# ESP32.net
KiCad netlist of a schematic drawn in Altium Designer
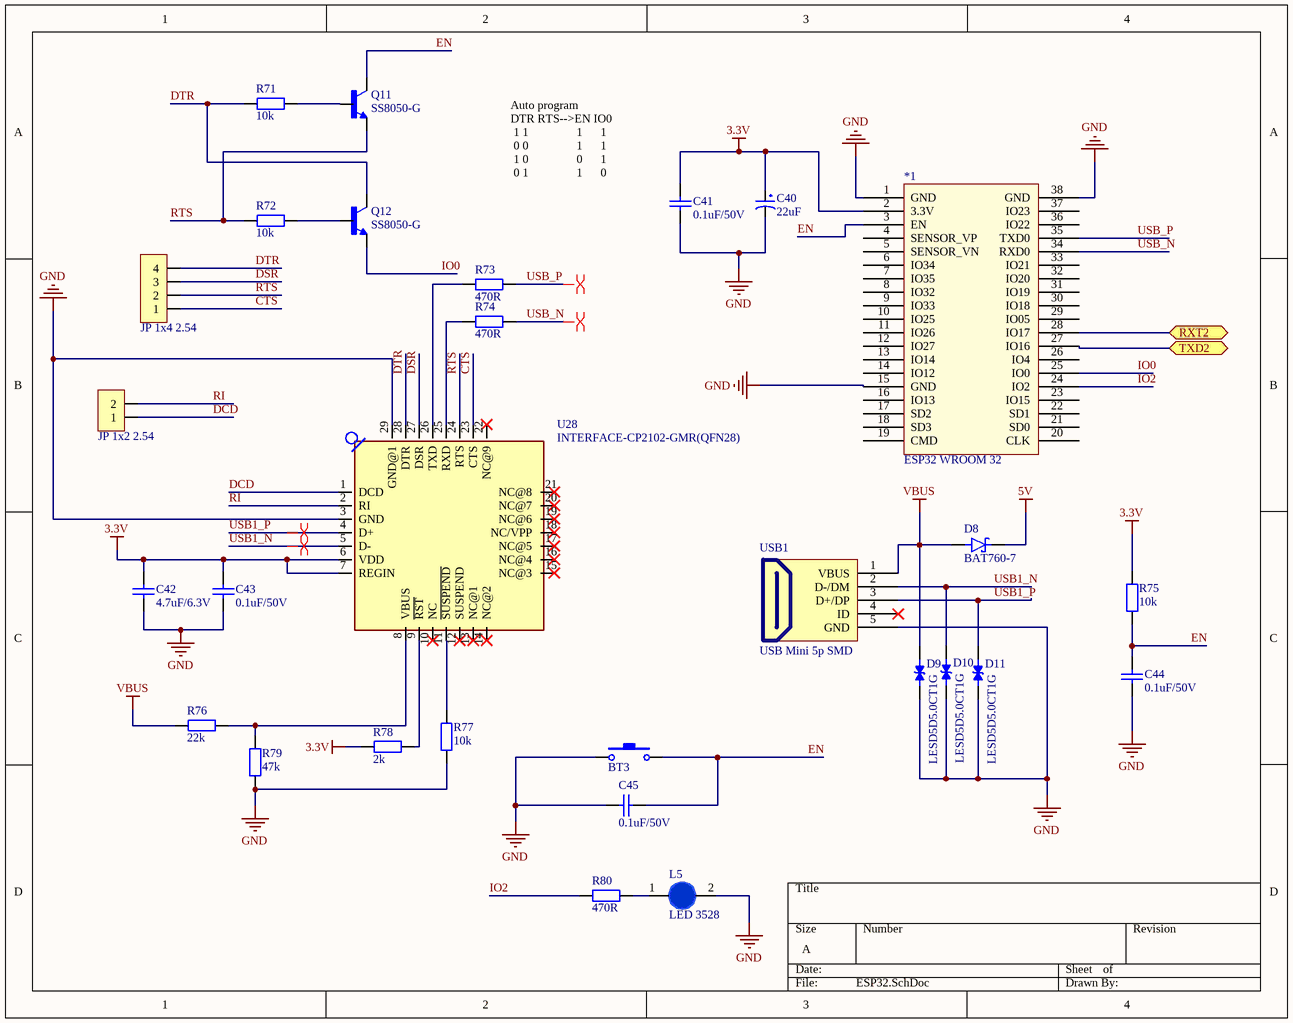
[diagram p0: ESP32.SchDoc]

(export (version "E")
  (design (tool "Eeschema 10.0.6"))
  (components
    (comp (ref "*1")
      (value "ESP32 WROOM 32")
      (footprint "ESP32-WROOM-32D")
      (libsource (lib "Altium_Lib_by_KhueNguyenCreator") (part "ESP32 WROOM 32"))
    )
    (comp (ref "BT3")
      (value "Nut Nhan 2 Chan SMD 3x6x2.5")
      (footprint "Nut Nhan 2 Chan SMD 3x6x2.5")
      (libsource (lib "Altium_Lib_by_KhueNguyenCreator") (part "Nut Nhan 2 Chan SMD 3x6x2.5"))
    )
    (comp (ref "C40")
      (value "22uF")
      (footprint "tu tantalum smd7343")
      (description "Dán")
      (libsource (lib "Altium_Lib_by_KhueNguyenCreator") (part "Tu tantalum 22uF 25V SMD7343"))
    )
    (comp (ref "C41")
      (value "0.1uF/50V")
      (footprint "tu 0805")
      (description "Dán")
      (libsource (lib "Altium_Lib_by_KhueNguyenCreator") (part "Tu 0805 104 50V 10%"))
    )
    (comp (ref "C42")
      (value "4.7uF/6.3V")
      (footprint "tu 0805")
      (description "Dán")
      (libsource (lib "Altium_Lib_by_KhueNguyenCreator") (part "Tu 0805 104 50V 10%"))
    )
    (comp (ref "C43")
      (value "0.1uF/50V")
      (footprint "tu 0805")
      (description "Dán")
      (libsource (lib "Altium_Lib_by_KhueNguyenCreator") (part "Tu 0805 104 50V 10%"))
    )
    (comp (ref "C44")
      (value "0.1uF/50V")
      (footprint "tu 0805")
      (description "Dán")
      (libsource (lib "Altium_Lib_by_KhueNguyenCreator") (part "Tu 0805 104 50V 10%"))
    )
    (comp (ref "C45")
      (value "0.1uF/50V")
      (footprint "tu 0805")
      (description "Dán")
      (libsource (lib "Altium_Lib_by_KhueNguyenCreator") (part "Tu 0805 104 50V 10%"))
    )
    (comp (ref "D8")
      (value "BAT760-7")
      (footprint "SOD2513X120N")
      (description "Diode Schottky 30V 1A 2-Pin SOD-323 T/R")
      (fields (field (name "MF") "Diodes Zetex"))
      (libsource (lib "TestLib") (part "BAT760-7"))
    )
    (comp (ref "D9")
      (value "LESD5D5.0CT1G")
      (footprint "TVS_LESD5D5.0CT1G")
      (description "Transient Voltage Suppressors for ESD Protection")
      (fields (field (name "MF") "Leshan Radio Co."))
      (libsource (lib "TestLib") (part "LESD5D5.0CT1G"))
    )
    (comp (ref "D10")
      (value "LESD5D5.0CT1G")
      (footprint "TVS_LESD5D5.0CT1G")
      (description "Transient Voltage Suppressors for ESD Protection")
      (fields (field (name "MF") "Leshan Radio Co."))
      (libsource (lib "TestLib") (part "LESD5D5.0CT1G"))
    )
    (comp (ref "D11")
      (value "LESD5D5.0CT1G")
      (footprint "TVS_LESD5D5.0CT1G")
      (description "Transient Voltage Suppressors for ESD Protection")
      (fields (field (name "MF") "Leshan Radio Co."))
      (libsource (lib "TestLib") (part "LESD5D5.0CT1G"))
    )
    (comp (ref "JP2")
      (value "JP 1x4 2.54")
      (footprint "JP 1x4 DT")
      (description "Cắm")
      (libsource (lib "Altium_Lib_by_KhueNguyenCreator") (part "JP 1x4 2.54 Duc Thang"))
    )
    (comp (ref "JP3")
      (value "JP 1x2 2.54")
      (footprint "JP 1x2 DT")
      (description "Cắm")
      (libsource (lib "Altium_Lib_by_KhueNguyenCreator") (part "JP 1x2 2.54 Duc Thang"))
    )
    (comp (ref "L5")
      (value "LED 3528")
      (footprint "LED-3528-BLUE")
      (description "Dán")
      (libsource (lib "Altium_Lib_by_KhueNguyenCreator") (part "LED 3528 Xanh Duong"))
    )
    (comp (ref "Q11")
      (value "SS8050-G")
      (footprint "TRANS_SS8050-G")
      (description "Bipolar (BJT) Transistor NPN 25 V 1.5 A 100MHz 300 mW Surface Mount SOT-23-3")
      (fields (field (name "DIGI-KEY_PART_NUMBER") "641-1790-2-ND") (field (name "MP") "SS8050G"))
      (libsource (lib "TestLib") (part "SS8050-G"))
    )
    (comp (ref "Q12")
      (value "SS8050-G")
      (footprint "TRANS_SS8050-G")
      (description "Bipolar (BJT) Transistor NPN 25 V 1.5 A 100MHz 300 mW Surface Mount SOT-23-3")
      (fields (field (name "DIGI-KEY_PART_NUMBER") "641-1790-2-ND") (field (name "MP") "SS8050G"))
      (libsource (lib "TestLib") (part "SS8050-G"))
    )
    (comp (ref "R71")
      (value "10k")
      (footprint "tro smd 0805")
      (description "Dán")
      (libsource (lib "Altium_Lib_by_KhueNguyenCreator") (part "Tro 0805 5% 10k"))
    )
    (comp (ref "R72")
      (value "10k")
      (footprint "tro smd 0805")
      (description "Dán")
      (libsource (lib "Altium_Lib_by_KhueNguyenCreator") (part "Tro 0805 5% 10k"))
    )
    (comp (ref "R73")
      (value "470R")
      (footprint "Tro SMD 0805")
      (description "Dán")
      (libsource (lib "Altium_Lib_by_KhueNguyenCreator") (part "Tro 0805 5% 470R"))
    )
    (comp (ref "R74")
      (value "470R")
      (footprint "Tro SMD 0805")
      (description "Dán")
      (libsource (lib "Altium_Lib_by_KhueNguyenCreator") (part "Tro 0805 5% 470R"))
    )
    (comp (ref "R75")
      (value "10k")
      (footprint "tro smd 0805")
      (description "Dán")
      (libsource (lib "Altium_Lib_by_KhueNguyenCreator") (part "Tro 0805 5% 10k"))
    )
    (comp (ref "R76")
      (value "22k")
      (footprint "tro smd 0805")
      (description "Dán")
      (libsource (lib "Altium_Lib_by_KhueNguyenCreator") (part "Tro 0805 5% 22k"))
    )
    (comp (ref "R77")
      (value "10k")
      (footprint "tro smd 0805")
      (description "Dán")
      (libsource (lib "Altium_Lib_by_KhueNguyenCreator") (part "Tro 0805 5% 10k"))
    )
    (comp (ref "R78")
      (value "2k")
      (footprint "Tro SMD 0805")
      (description "Dán")
      (libsource (lib "Altium_Lib_by_KhueNguyenCreator") (part "Tro 0805 5% 2k"))
    )
    (comp (ref "R79")
      (value "47k")
      (footprint "tro smd 0805")
      (description "Dán")
      (libsource (lib "Altium_Lib_by_KhueNguyenCreator") (part "Tro 0805 5% 47k"))
    )
    (comp (ref "R80")
      (value "470R")
      (footprint "Tro SMD 0805")
      (description "Dán")
      (libsource (lib "Altium_Lib_by_KhueNguyenCreator") (part "Tro 0805 5% 470R"))
    )
    (comp (ref "U28")
      (value "INTERFACE-CP2102-GMR(QFN28)")
      (footprint "QFN28G_0.5-5X5MM")
      (description "USB Bridge, USB to UART USB 2.0 UART Interface 28-QFN (5x5)")
      (fields (field (name "MP") "CP2102-GMR") (field (name "MF") "Silicon"))
      (libsource (lib "TestLib") (part "INTERFACE-CP2102-GMR(QFN28)"))
    )
    (comp (ref "USB1")
      (value "USB Mini 5p SMD")
      (footprint "USB Mini 5p SMD")
      (description "USB Type B")
      (libsource (lib "Altium_Lib_by_KhueNguyenCreator") (part "USB Mini 5p SMD"))
    )
  )
  (nets
    (net (code "1") (name "/CTS") (class "Default")
      (node (ref "JP2") (pin "1") (pinfunction "1_1") (pintype "passive"))
      (node (ref "U28") (pin "23") (pinfunction "CTS_23") (pintype "bidirectional"))
    )
    (net (code "2") (name "/DCD") (class "Default")
      (node (ref "JP3") (pin "1") (pinfunction "1_1") (pintype "passive"))
      (node (ref "U28") (pin "1") (pinfunction "DCD_1") (pintype "bidirectional"))
    )
    (net (code "3") (name "/DSR") (class "Default")
      (node (ref "JP2") (pin "3") (pinfunction "3_3") (pintype "passive"))
      (node (ref "U28") (pin "27") (pinfunction "DSR_27") (pintype "bidirectional"))
    )
    (net (code "4") (name "/DTR") (class "Default")
      (node (ref "JP2") (pin "4") (pinfunction "4_4") (pintype "passive"))
      (node (ref "Q12") (pin "3") (pinfunction "C_3") (pintype "passive"))
      (node (ref "R71") (pin "1") (pinfunction "1_1") (pintype "passive"))
      (node (ref "U28") (pin "28") (pinfunction "DTR_28") (pintype "bidirectional"))
    )
    (net (code "5") (name "/EN") (class "Default")
      (node (ref "*1") (pin "3") (pinfunction "EN_3") (pintype "passive"))
      (node (ref "BT3") (pin "2") (pinfunction "2_2") (pintype "passive"))
      (node (ref "C44") (pin "2") (pinfunction "2_2") (pintype "passive"))
      (node (ref "C45") (pin "1") (pinfunction "1_1") (pintype "passive"))
      (node (ref "Q11") (pin "3") (pinfunction "C_3") (pintype "passive"))
      (node (ref "R75") (pin "1") (pinfunction "1_1") (pintype "passive"))
    )
    (net (code "6") (name "/IO0") (class "Default")
      (node (ref "*1") (pin "25") (pinfunction "IO0_25") (pintype "passive"))
      (node (ref "Q12") (pin "2") (pinfunction "E_2") (pintype "passive"))
    )
    (net (code "7") (name "/IO2") (class "Default")
      (node (ref "*1") (pin "24") (pinfunction "IO2_24") (pintype "passive"))
      (node (ref "R80") (pin "1") (pinfunction "1_1") (pintype "passive"))
    )
    (net (code "8") (name "/RI") (class "Default")
      (node (ref "JP3") (pin "2") (pinfunction "2_2") (pintype "passive"))
      (node (ref "U28") (pin "2") (pinfunction "RI_2") (pintype "bidirectional"))
    )
    (net (code "9") (name "/RTS") (class "Default")
      (node (ref "JP2") (pin "2") (pinfunction "2_2") (pintype "passive"))
      (node (ref "Q11") (pin "2") (pinfunction "E_2") (pintype "passive"))
      (node (ref "R72") (pin "1") (pinfunction "1_1") (pintype "passive"))
      (node (ref "U28") (pin "24") (pinfunction "RTS_24") (pintype "bidirectional"))
    )
    (net (code "10") (name "/RXT2") (class "Default")
      (node (ref "*1") (pin "28") (pinfunction "IO17_28") (pintype "passive"))
    )
    (net (code "11") (name "/TXD2") (class "Default")
      (node (ref "*1") (pin "27") (pinfunction "IO16_27") (pintype "passive"))
    )
    (net (code "12") (name "/USB1_N") (class "Default")
      (node (ref "D10") (pin "1") (pinfunction "1_1") (pintype "passive"))
      (node (ref "U28") (pin "5") (pinfunction "D-_5") (pintype "bidirectional"))
      (node (ref "USB1") (pin "2") (pinfunction "D-/DM_2") (pintype "passive"))
    )
    (net (code "13") (name "/USB1_P") (class "Default")
      (node (ref "D11") (pin "1") (pinfunction "1_1") (pintype "passive"))
      (node (ref "U28") (pin "4") (pinfunction "D+_4") (pintype "bidirectional"))
      (node (ref "USB1") (pin "3") (pinfunction "D+/DP_3") (pintype "passive"))
    )
    (net (code "14") (name "/USB_N") (class "Default")
      (node (ref "*1") (pin "34") (pinfunction "RXD0_34") (pintype "passive"))
      (node (ref "R74") (pin "2") (pinfunction "2_2") (pintype "passive"))
    )
    (net (code "15") (name "/USB_P") (class "Default")
      (node (ref "*1") (pin "35") (pinfunction "TXD0_35") (pintype "passive"))
      (node (ref "R73") (pin "2") (pinfunction "2_2") (pintype "passive"))
    )
    (net (code "16") (name "3.3V") (class "Default")
      (node (ref "*1") (pin "2") (pinfunction "3.3V_2") (pintype "passive"))
      (node (ref "C40") (pin "1") (pinfunction "1_1") (pintype "passive"))
      (node (ref "C41") (pin "2") (pinfunction "2_2") (pintype "passive"))
      (node (ref "C42") (pin "1") (pinfunction "1_1") (pintype "passive"))
      (node (ref "C43") (pin "1") (pinfunction "1_1") (pintype "passive"))
      (node (ref "R75") (pin "2") (pinfunction "2_2") (pintype "passive"))
      (node (ref "R78") (pin "1") (pinfunction "1_1") (pintype "passive"))
      (node (ref "U28") (pin "6") (pinfunction "VDD_6") (pintype "bidirectional"))
      (node (ref "U28") (pin "7") (pinfunction "REGIN_7") (pintype "bidirectional"))
    )
    (net (code "17") (name "5V") (class "Default")
      (node (ref "D8") (pin "C") (pinfunction "K_C") (pintype "passive"))
    )
    (net (code "18") (name "GND") (class "Default")
      (node (ref "*1") (pin "1") (pinfunction "GND_1") (pintype "passive"))
      (node (ref "*1") (pin "15") (pinfunction "GND_15") (pintype "passive"))
      (node (ref "*1") (pin "38") (pinfunction "GND_38") (pintype "passive"))
      (node (ref "BT3") (pin "1") (pinfunction "1_1") (pintype "passive"))
      (node (ref "C40") (pin "2") (pinfunction "2_2") (pintype "passive"))
      (node (ref "C41") (pin "1") (pinfunction "1_1") (pintype "passive"))
      (node (ref "C42") (pin "2") (pinfunction "2_2") (pintype "passive"))
      (node (ref "C43") (pin "2") (pinfunction "2_2") (pintype "passive"))
      (node (ref "C44") (pin "1") (pinfunction "1_1") (pintype "passive"))
      (node (ref "C45") (pin "2") (pinfunction "2_2") (pintype "passive"))
      (node (ref "D10") (pin "2") (pinfunction "2_2") (pintype "passive"))
      (node (ref "D11") (pin "2") (pinfunction "2_2") (pintype "passive"))
      (node (ref "D9") (pin "2") (pinfunction "2_2") (pintype "passive"))
      (node (ref "L5") (pin "2") (pinfunction "K_2") (pintype "passive"))
      (node (ref "R77") (pin "1") (pinfunction "1_1") (pintype "passive"))
      (node (ref "R79") (pin "2") (pinfunction "2_2") (pintype "passive"))
      (node (ref "U28") (pin "29") (pinfunction "GND@1_29") (pintype "bidirectional"))
      (node (ref "U28") (pin "3") (pinfunction "GND_3") (pintype "bidirectional"))
      (node (ref "USB1") (pin "5") (pinfunction "GND_5") (pintype "passive"))
    )
    (net (code "19") (name "Net-(L5-A)") (class "Default")
      (node (ref "L5") (pin "1") (pinfunction "A_1") (pintype "passive"))
      (node (ref "R80") (pin "2") (pinfunction "2_2") (pintype "passive"))
    )
    (net (code "20") (name "Net-(Q11-B)") (class "Default")
      (node (ref "Q11") (pin "1") (pinfunction "B_1") (pintype "passive"))
      (node (ref "R71") (pin "2") (pinfunction "2_2") (pintype "passive"))
    )
    (net (code "21") (name "Net-(Q12-B)") (class "Default")
      (node (ref "Q12") (pin "1") (pinfunction "B_1") (pintype "passive"))
      (node (ref "R72") (pin "2") (pinfunction "2_2") (pintype "passive"))
    )
    (net (code "22") (name "Net-(U28-RXD)") (class "Default")
      (node (ref "R74") (pin "1") (pinfunction "1_1") (pintype "passive"))
      (node (ref "U28") (pin "25") (pinfunction "RXD_25") (pintype "bidirectional"))
    )
    (net (code "23") (name "Net-(U28-TXD)") (class "Default")
      (node (ref "R73") (pin "1") (pinfunction "1_1") (pintype "passive"))
      (node (ref "U28") (pin "26") (pinfunction "TXD_26") (pintype "bidirectional"))
    )
    (net (code "24") (name "Net-(U28-VBUS)") (class "Default")
      (node (ref "R76") (pin "2") (pinfunction "2_2") (pintype "passive"))
      (node (ref "R79") (pin "1") (pinfunction "1_1") (pintype "passive"))
      (node (ref "U28") (pin "8") (pinfunction "VBUS_8") (pintype "bidirectional"))
    )
    (net (code "25") (name "Net-(U28-~{RST})") (class "Default")
      (node (ref "R78") (pin "2") (pinfunction "2_2") (pintype "passive"))
      (node (ref "U28") (pin "9") (pinfunction "~{RST}_9") (pintype "bidirectional"))
    )
    (net (code "26") (name "Net-(U28-~{SUSPEND})") (class "Default")
      (node (ref "R77") (pin "2") (pinfunction "2_2") (pintype "passive"))
      (node (ref "U28") (pin "11") (pinfunction "~{SUSPEND}_11") (pintype "bidirectional"))
    )
    (net (code "27") (name "VBUS") (class "Default")
      (node (ref "D8") (pin "A") (pinfunction "A_A") (pintype "passive"))
      (node (ref "D9") (pin "1") (pinfunction "1_1") (pintype "passive"))
      (node (ref "R76") (pin "1") (pinfunction "1_1") (pintype "passive"))
      (node (ref "USB1") (pin "1") (pinfunction "VBUS_1") (pintype "passive"))
    )
    (net (code "28") (name "unconnected-(*1-CLK-Pad20)") (class "Default")
      (node (ref "*1") (pin "20") (pinfunction "CLK_20") (pintype "passive"))
    )
    (net (code "29") (name "unconnected-(*1-CMD-Pad19)") (class "Default")
      (node (ref "*1") (pin "19") (pinfunction "CMD_19") (pintype "passive"))
    )
    (net (code "30") (name "unconnected-(*1-IO4-Pad26)") (class "Default")
      (node (ref "*1") (pin "26") (pinfunction "IO4_26") (pintype "passive"))
    )
    (net (code "31") (name "unconnected-(*1-IO05-Pad29)") (class "Default")
      (node (ref "*1") (pin "29") (pinfunction "IO05_29") (pintype "passive"))
    )
    (net (code "32") (name "unconnected-(*1-IO12-Pad14)") (class "Default")
      (node (ref "*1") (pin "14") (pinfunction "IO12_14") (pintype "passive"))
    )
    (net (code "33") (name "unconnected-(*1-IO13-Pad16)") (class "Default")
      (node (ref "*1") (pin "16") (pinfunction "IO13_16") (pintype "passive"))
    )
    (net (code "34") (name "unconnected-(*1-IO14-Pad13)") (class "Default")
      (node (ref "*1") (pin "13") (pinfunction "IO14_13") (pintype "passive"))
    )
    (net (code "35") (name "unconnected-(*1-IO15-Pad23)") (class "Default")
      (node (ref "*1") (pin "23") (pinfunction "IO15_23") (pintype "passive"))
    )
    (net (code "36") (name "unconnected-(*1-IO18-Pad30)") (class "Default")
      (node (ref "*1") (pin "30") (pinfunction "IO18_30") (pintype "passive"))
    )
    (net (code "37") (name "unconnected-(*1-IO19-Pad31)") (class "Default")
      (node (ref "*1") (pin "31") (pinfunction "IO19_31") (pintype "passive"))
    )
    (net (code "38") (name "unconnected-(*1-IO20-Pad32)") (class "Default")
      (node (ref "*1") (pin "32") (pinfunction "IO20_32") (pintype "passive"))
    )
    (net (code "39") (name "unconnected-(*1-IO21-Pad33)") (class "Default")
      (node (ref "*1") (pin "33") (pinfunction "IO21_33") (pintype "passive"))
    )
    (net (code "40") (name "unconnected-(*1-IO22-Pad36)") (class "Default")
      (node (ref "*1") (pin "36") (pinfunction "IO22_36") (pintype "passive"))
    )
    (net (code "41") (name "unconnected-(*1-IO23-Pad37)") (class "Default")
      (node (ref "*1") (pin "37") (pinfunction "IO23_37") (pintype "passive"))
    )
    (net (code "42") (name "unconnected-(*1-IO25-Pad10)") (class "Default")
      (node (ref "*1") (pin "10") (pinfunction "IO25_10") (pintype "passive"))
    )
    (net (code "43") (name "unconnected-(*1-IO26-Pad11)") (class "Default")
      (node (ref "*1") (pin "11") (pinfunction "IO26_11") (pintype "passive"))
    )
    (net (code "44") (name "unconnected-(*1-IO27-Pad12)") (class "Default")
      (node (ref "*1") (pin "12") (pinfunction "IO27_12") (pintype "passive"))
    )
    (net (code "45") (name "unconnected-(*1-IO32-Pad8)") (class "Default")
      (node (ref "*1") (pin "8") (pinfunction "IO32_8") (pintype "passive"))
    )
    (net (code "46") (name "unconnected-(*1-IO33-Pad9)") (class "Default")
      (node (ref "*1") (pin "9") (pinfunction "IO33_9") (pintype "passive"))
    )
    (net (code "47") (name "unconnected-(*1-IO34-Pad6)") (class "Default")
      (node (ref "*1") (pin "6") (pinfunction "IO34_6") (pintype "passive"))
    )
    (net (code "48") (name "unconnected-(*1-IO35-Pad7)") (class "Default")
      (node (ref "*1") (pin "7") (pinfunction "IO35_7") (pintype "passive"))
    )
    (net (code "49") (name "unconnected-(*1-SD0-Pad21)") (class "Default")
      (node (ref "*1") (pin "21") (pinfunction "SD0_21") (pintype "passive"))
    )
    (net (code "50") (name "unconnected-(*1-SD1-Pad22)") (class "Default")
      (node (ref "*1") (pin "22") (pinfunction "SD1_22") (pintype "passive"))
    )
    (net (code "51") (name "unconnected-(*1-SD2-Pad17)") (class "Default")
      (node (ref "*1") (pin "17") (pinfunction "SD2_17") (pintype "passive"))
    )
    (net (code "52") (name "unconnected-(*1-SD3-Pad18)") (class "Default")
      (node (ref "*1") (pin "18") (pinfunction "SD3_18") (pintype "passive"))
    )
    (net (code "53") (name "unconnected-(*1-SENSOR_VN-Pad5)") (class "Default")
      (node (ref "*1") (pin "5") (pinfunction "SENSOR_VN_5") (pintype "passive"))
    )
    (net (code "54") (name "unconnected-(*1-SENSOR_VP-Pad4)") (class "Default")
      (node (ref "*1") (pin "4") (pinfunction "SENSOR_VP_4") (pintype "passive"))
    )
    (net (code "55") (name "unconnected-(U28-NC-Pad10)") (class "Default")
      (node (ref "U28") (pin "10") (pinfunction "NC_10") (pintype "bidirectional+no_connect"))
    )
    (net (code "56") (name "unconnected-(U28-NC@1-Pad13)") (class "Default")
      (node (ref "U28") (pin "13") (pinfunction "NC@1_13") (pintype "bidirectional+no_connect"))
    )
    (net (code "57") (name "unconnected-(U28-NC@2-Pad14)") (class "Default")
      (node (ref "U28") (pin "14") (pinfunction "NC@2_14") (pintype "bidirectional+no_connect"))
    )
    (net (code "58") (name "unconnected-(U28-NC@3-Pad15)") (class "Default")
      (node (ref "U28") (pin "15") (pinfunction "NC@3_15") (pintype "bidirectional+no_connect"))
    )
    (net (code "59") (name "unconnected-(U28-NC@4-Pad16)") (class "Default")
      (node (ref "U28") (pin "16") (pinfunction "NC@4_16") (pintype "bidirectional+no_connect"))
    )
    (net (code "60") (name "unconnected-(U28-NC@5-Pad17)") (class "Default")
      (node (ref "U28") (pin "17") (pinfunction "NC@5_17") (pintype "bidirectional+no_connect"))
    )
    (net (code "61") (name "unconnected-(U28-NC@6-Pad19)") (class "Default")
      (node (ref "U28") (pin "19") (pinfunction "NC@6_19") (pintype "bidirectional+no_connect"))
    )
    (net (code "62") (name "unconnected-(U28-NC@7-Pad20)") (class "Default")
      (node (ref "U28") (pin "20") (pinfunction "NC@7_20") (pintype "bidirectional+no_connect"))
    )
    (net (code "63") (name "unconnected-(U28-NC@8-Pad21)") (class "Default")
      (node (ref "U28") (pin "21") (pinfunction "NC@8_21") (pintype "bidirectional+no_connect"))
    )
    (net (code "64") (name "unconnected-(U28-NC@9-Pad22)") (class "Default")
      (node (ref "U28") (pin "22") (pinfunction "NC@9_22") (pintype "bidirectional+no_connect"))
    )
    (net (code "65") (name "unconnected-(U28-NC{slash}VPP-Pad18)") (class "Default")
      (node (ref "U28") (pin "18") (pinfunction "NC/VPP_18") (pintype "bidirectional+no_connect"))
    )
    (net (code "66") (name "unconnected-(U28-SUSPEND-Pad12)") (class "Default")
      (node (ref "U28") (pin "12") (pinfunction "SUSPEND_12") (pintype "bidirectional+no_connect"))
    )
    (net (code "67") (name "unconnected-(USB1-ID-Pad4)") (class "Default")
      (node (ref "USB1") (pin "4") (pinfunction "ID_4") (pintype "passive+no_connect"))
    )
  )
)
